# Arduino-RedBoard.net
KiCad netlist of a schematic drawn in Altium Designer
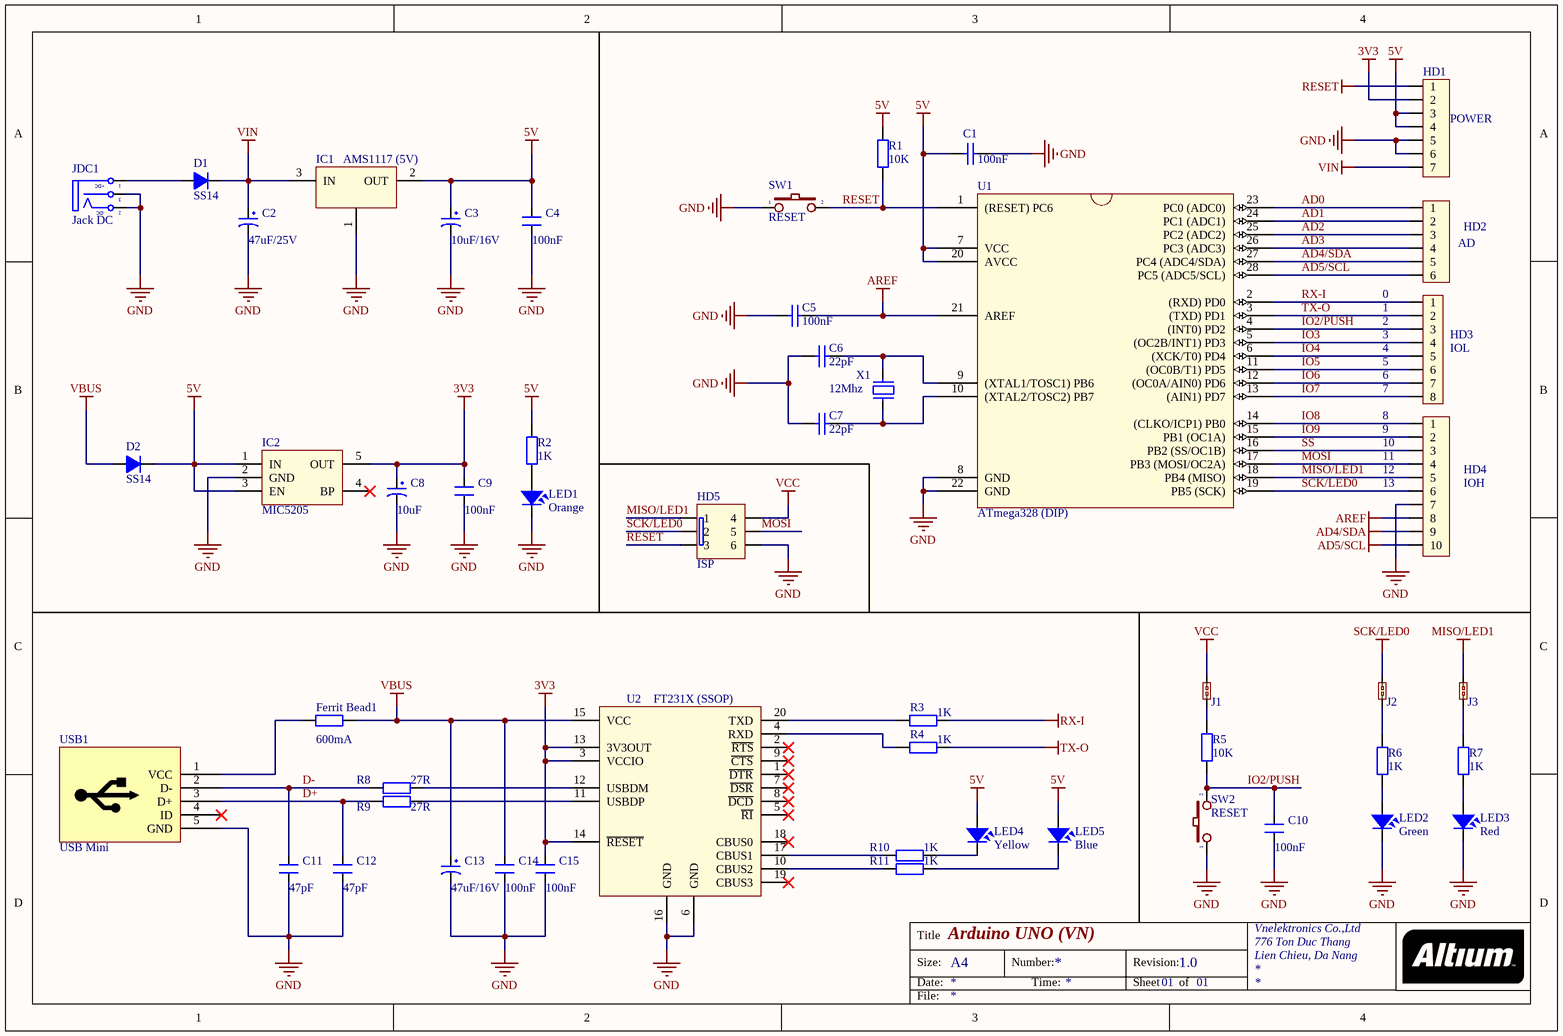
[diagram p0: Arduino-RedBoard.SchDoc]

(export (version "E")
  (design (tool "Eeschema 10.0.6"))
  (components
    (comp (ref "C1")
      (value "100nF")
      (footprint "CAPNTO2.54-3.05x1.78A")
      (description "CAP NPO CAPNTO 1nF 100V 10%")
      (fields (field (name "Comment") "5AK102KABAA"))
      (libsource (lib "lpson") (part "5AK102KABAA"))
    )
    (comp (ref "C2") (value "47uF/25V") (footprint "CP1/2") (libsource (lib "VNELEK") (part "CP1")))
    (comp (ref "C3")
      (value "10uF/16V")
      (footprint "CP1/2")
      (description "Cap P  0,1uF < 22uF , 16 - 50V")
      (libsource (lib "VNELEK") (part "CP1"))
    )
    (comp (ref "C4")
      (value "100nF")
      (footprint "CN2")
      (description "Cap np 104 => 105pF")
      (libsource (lib "VNELEK") (part "CN2"))
    )
    (comp (ref "C5")
      (value "100nF")
      (footprint "CAPNTO2.54-3.05x1.78A")
      (description "CAP NPO CAPNTO 1nF 100V 10%")
      (fields (field (name "Comment") "5AK102KABAA"))
      (libsource (lib "lpson") (part "5AK102KABAA"))
    )
    (comp (ref "C6")
      (value "22pF")
      (footprint "CAPNTO2.54-3.05x1.78A")
      (description "CAP NPO CAPNTO 1nF 100V 10%")
      (fields (field (name "Comment") "5AK102KABAA"))
      (libsource (lib "lpson") (part "5AK102KABAA"))
    )
    (comp (ref "C7")
      (value "22pF")
      (footprint "CAPNTO2.54-3.05x1.78A")
      (description "CAP NPO CAPNTO 1nF 100V 10%")
      (fields (field (name "Comment") "5AK102KABAA"))
      (libsource (lib "lpson") (part "5AK102KABAA"))
    )
    (comp (ref "C8")
      (value "10uF")
      (footprint "CP1/2")
      (description "Cap P  0,1uF < 22uF , 16 - 50V")
      (libsource (lib "VNELEK") (part "CP1"))
    )
    (comp (ref "C9")
      (value "100nF")
      (footprint "CN2")
      (description "Cap np 104 => 105pF")
      (libsource (lib "VNELEK") (part "CN2"))
    )
    (comp (ref "C10")
      (value "100nF")
      (footprint "CN2")
      (description "Cap np 104 => 105pF")
      (libsource (lib "VNELEK") (part "CN2"))
    )
    (comp (ref "C11")
      (value "47pF")
      (footprint "CN2")
      (description "Cap np 104 => 105pF")
      (libsource (lib "VNELEK") (part "CN2"))
    )
    (comp (ref "C12")
      (value "47pF")
      (footprint "CN2")
      (description "Cap np 104 => 105pF")
      (libsource (lib "VNELEK") (part "CN2"))
    )
    (comp (ref "C13") (value "47uF/16V") (footprint "CP1/2") (libsource (lib "VNELEK") (part "CP1")))
    (comp (ref "C14")
      (value "100nF")
      (footprint "CN2")
      (description "Cap np 104 => 105pF")
      (libsource (lib "VNELEK") (part "CN2"))
    )
    (comp (ref "C15")
      (value "100nF")
      (footprint "CN2")
      (description "Cap np 104 => 105pF")
      (libsource (lib "VNELEK") (part "CN2"))
    )
    (comp (ref "D1")
      (value "SS14")
      (footprint "D1A")
      (description "Diode 1A")
      (libsource (lib "VNELEK") (part "D1A"))
    )
    (comp (ref "D2")
      (value "SS14")
      (footprint "D1A")
      (description "Diode 1A")
      (libsource (lib "VNELEK") (part "D1A"))
    )
    (comp (ref "Ferrit Bead1")
      (value "600mA")
      (footprint "AXIAL-0.4")
      (description "Ferrit Bead")
      (libsource (lib "") (part "Res2_2"))
    )
    (comp (ref "HD1") (value "POWER") (description "Header 7") (libsource (lib "Tran Tuan") (part "Hed7")))
    (comp (ref "HD2") (value "AD") (description "Header 6") (libsource (lib "Tran Tuan") (part "Hed6")))
    (comp (ref "HD3")
      (value "IOL")
      (footprint "HED8")
      (description "Hedear 8")
      (fields (field (name "CREAT BY") "VanDungEvn@Gmail.com"))
      (libsource (lib "VNELEK") (part "Hed8"))
    )
    (comp (ref "HD4") (value "IOH") (description "Header 10") (libsource (lib "Tran Tuan") (part "Hed10")))
    (comp (ref "HD5") (value "ISP") (description "Header 3x2") (libsource (lib "Tran Tuan") (part "HED3x2")))
    (comp (ref "IC1")
      (value "AMS1117 (5V)")
      (description "1A LOW DROPOUT VOLTAGE REGULATOR")
      (libsource (lib "Tran Tuan") (part "AMS1117"))
    )
    (comp (ref "IC2")
      (value "MIC5205")
      (description "150mA Low  -  Noise LDO Regulator")
      (libsource (lib "Tran Tuan") (part "MIC5205"))
    )
    (comp (ref "J1") (value "Short Jump") (libsource (lib "Tran Tuan") (part "ShortJump")))
    (comp (ref "J2") (value "Short Jump") (libsource (lib "Tran Tuan") (part "ShortJump")))
    (comp (ref "J3") (value "Short Jump") (libsource (lib "Tran Tuan") (part "ShortJump")))
    (comp (ref "JDC1")
      (value "Jack DC")
      (footprint "DC-IN")
      (description "Jac DC input")
      (libsource (lib "VNELEK") (part "DCIN"))
    )
    (comp (ref "LED1")
      (value "Orange")
      (footprint "LED-3")
      (description "LED Single colour Green and Red")
      (libsource (lib "VNELEK") (part "LED"))
    )
    (comp (ref "LED2")
      (value "Green")
      (footprint "LED-3")
      (description "LED Single colour Green and Red")
      (libsource (lib "VNELEK") (part "LED"))
    )
    (comp (ref "LED3")
      (value "Red")
      (footprint "LED-3")
      (description "LED Single colour Green and Red")
      (libsource (lib "VNELEK") (part "LED"))
    )
    (comp (ref "LED4")
      (value "Yellow")
      (footprint "LED-3")
      (description "LED Single colour Green and Red")
      (libsource (lib "VNELEK") (part "LED"))
    )
    (comp (ref "LED5")
      (value "Blue")
      (footprint "LED-3")
      (description "LED Single colour Green and Red")
      (libsource (lib "VNELEK") (part "LED"))
    )
    (comp (ref "R1")
      (value "10K")
      (footprint "AXIAL-0.4")
      (description "Resistor")
      (fields (field (name "Comment") "Res2") (field (name "PUBLISHER") "Altium Limited"))
      (libsource (lib "Miscellaneous Devices") (part "Res2"))
    )
    (comp (ref "R2")
      (value "1K")
      (footprint "AXIAL-0.4")
      (description "Resistor")
      (fields (field (name "Comment") "Res2") (field (name "PUBLISHER") "Altium Limited"))
      (libsource (lib "Miscellaneous Devices") (part "Res2"))
    )
    (comp (ref "R3")
      (value "1K")
      (footprint "AXIAL-0.4")
      (description "Resistor")
      (fields (field (name "Comment") "Res2") (field (name "PUBLISHER") "Altium Limited"))
      (libsource (lib "") (part "Res2_2"))
    )
    (comp (ref "R4")
      (value "1K")
      (footprint "AXIAL-0.4")
      (description "Resistor")
      (fields (field (name "Comment") "Res2") (field (name "PUBLISHER") "Altium Limited"))
      (libsource (lib "") (part "Res2_2"))
    )
    (comp (ref "R5")
      (value "10K")
      (footprint "AXIAL-0.4")
      (description "Resistor")
      (fields (field (name "Comment") "Res2") (field (name "PUBLISHER") "Altium Limited"))
      (libsource (lib "Miscellaneous Devices") (part "Res2"))
    )
    (comp (ref "R6")
      (value "1K")
      (footprint "AXIAL-0.4")
      (description "Resistor")
      (fields (field (name "Comment") "Res2") (field (name "PUBLISHER") "Altium Limited"))
      (libsource (lib "Miscellaneous Devices") (part "Res2"))
    )
    (comp (ref "R7")
      (value "1K")
      (footprint "AXIAL-0.4")
      (description "Resistor")
      (fields (field (name "Comment") "Res2") (field (name "PUBLISHER") "Altium Limited"))
      (libsource (lib "Miscellaneous Devices") (part "Res2"))
    )
    (comp (ref "R8")
      (value "27R")
      (footprint "AXIAL-0.4")
      (description "Resistor")
      (fields (field (name "Comment") "Res2") (field (name "PUBLISHER") "Altium Limited"))
      (libsource (lib "") (part "Res2_1"))
    )
    (comp (ref "R9")
      (value "27R")
      (footprint "AXIAL-0.4")
      (description "Resistor")
      (fields (field (name "Comment") "Res2") (field (name "PUBLISHER") "Altium Limited"))
      (libsource (lib "") (part "Res2_1"))
    )
    (comp (ref "R10")
      (value "1K")
      (footprint "AXIAL-0.4")
      (description "Resistor")
      (fields (field (name "Comment") "Res2") (field (name "PUBLISHER") "Altium Limited"))
      (libsource (lib "") (part "Res2_1"))
    )
    (comp (ref "R11")
      (value "1K")
      (footprint "AXIAL-0.4")
      (description "Resistor")
      (fields (field (name "Comment") "Res2") (field (name "PUBLISHER") "Altium Limited"))
      (libsource (lib "") (part "Res2_1"))
    )
    (comp (ref "SW1")
      (value "RESET")
      (footprint "SW2")
      (description "Switch button 2 pin")
      (libsource (lib "VNELEK") (part "SW2"))
    )
    (comp (ref "SW2")
      (value "RESET")
      (footprint "SW2")
      (description "Switch button 2 pin")
      (libsource (lib "VNELEK") (part "SW2"))
    )
    (comp (ref "U1")
      (value "ATmega328 (DIP)")
      (description "Atmel 8-bit Microcontroller")
      (libsource (lib "Tran Tuan") (part "ATmega328_1"))
    )
    (comp (ref "U2")
      (value "FT231X (SSOP)")
      (description "FT231Z (SSOP) - USB to UART")
      (libsource (lib "Tran Tuan") (part "FT231X"))
    )
    (comp (ref "USB1") (value "USB Mini") (footprint "USB_B_MINI") (libsource (lib "VNELEK") (part "USB_M")))
    (comp (ref "X1")
      (value "12Mhz")
      (footprint "CRYSTAL")
      (description "Crystal For all Crystal 2pin.")
      (libsource (lib "lpson") (part "XT2"))
    )
  )
  (nets
    (net (code "1") (name "/AD0") (class "Default")
      (node (ref "HD2") (pin "1") (pinfunction "1_1") (pintype "passive"))
      (node (ref "U1") (pin "23") (pinfunction "PC0_(ADC0)_23") (pintype "bidirectional"))
    )
    (net (code "2") (name "/AD1") (class "Default")
      (node (ref "HD2") (pin "2") (pinfunction "2_2") (pintype "passive"))
      (node (ref "U1") (pin "24") (pinfunction "PC1_(ADC1)_24") (pintype "bidirectional"))
    )
    (net (code "3") (name "/AD2") (class "Default")
      (node (ref "HD2") (pin "3") (pinfunction "3_3") (pintype "passive"))
      (node (ref "U1") (pin "25") (pinfunction "PC2_(ADC2)_25") (pintype "bidirectional"))
    )
    (net (code "4") (name "/AD3") (class "Default")
      (node (ref "HD2") (pin "4") (pinfunction "4_4") (pintype "passive"))
      (node (ref "U1") (pin "26") (pinfunction "PC3_(ADC3)_26") (pintype "bidirectional"))
    )
    (net (code "5") (name "/D+") (class "Default")
      (node (ref "C12") (pin "2") (pinfunction "2_2") (pintype "passive"))
      (node (ref "R9") (pin "2") (pinfunction "2_2") (pintype "passive"))
      (node (ref "USB1") (pin "3") (pinfunction "D+_3") (pintype "passive"))
    )
    (net (code "6") (name "/D-") (class "Default")
      (node (ref "C11") (pin "2") (pinfunction "2_2") (pintype "passive"))
      (node (ref "R8") (pin "2") (pinfunction "2_2") (pintype "passive"))
      (node (ref "USB1") (pin "2") (pinfunction "D-_2") (pintype "passive"))
    )
    (net (code "7") (name "/IO2{slash}PUSH") (class "Default")
      (node (ref "C10") (pin "2") (pinfunction "2_2") (pintype "passive"))
      (node (ref "HD3") (pin "3") (pinfunction "3_3") (pintype "passive"))
      (node (ref "R5") (pin "1") (pinfunction "1_1") (pintype "passive"))
      (node (ref "SW2") (pin "2") (pinfunction "2_2") (pintype "passive"))
      (node (ref "U1") (pin "4") (pinfunction "(INT0)_PD2_4") (pintype "bidirectional"))
    )
    (net (code "8") (name "/IO3") (class "Default")
      (node (ref "HD3") (pin "4") (pinfunction "4_4") (pintype "passive"))
      (node (ref "U1") (pin "5") (pinfunction "(OC2B/INT1)_PD3_5") (pintype "bidirectional"))
    )
    (net (code "9") (name "/IO4") (class "Default")
      (node (ref "HD3") (pin "5") (pinfunction "5_5") (pintype "passive"))
      (node (ref "U1") (pin "6") (pinfunction "(XCK/T0)_PD4_6") (pintype "bidirectional"))
    )
    (net (code "10") (name "/IO5") (class "Default")
      (node (ref "HD3") (pin "6") (pinfunction "6_6") (pintype "passive"))
      (node (ref "U1") (pin "11") (pinfunction "(OC0B/T1)_PD5_11") (pintype "bidirectional"))
    )
    (net (code "11") (name "/IO6") (class "Default")
      (node (ref "HD3") (pin "7") (pinfunction "7_7") (pintype "passive"))
      (node (ref "U1") (pin "12") (pinfunction "(OC0A/AIN0)_PD6_12") (pintype "bidirectional"))
    )
    (net (code "12") (name "/IO7") (class "Default")
      (node (ref "HD3") (pin "8") (pinfunction "8_8") (pintype "passive"))
      (node (ref "U1") (pin "13") (pinfunction "(AIN1)_PD7_13") (pintype "bidirectional"))
    )
    (net (code "13") (name "/IO8") (class "Default")
      (node (ref "HD4") (pin "1") (pinfunction "1_1") (pintype "passive"))
      (node (ref "U1") (pin "14") (pinfunction "(CLKO/ICP1)_PB0_14") (pintype "bidirectional"))
    )
    (net (code "14") (name "/IO9") (class "Default")
      (node (ref "HD4") (pin "2") (pinfunction "2_2") (pintype "passive"))
      (node (ref "U1") (pin "15") (pinfunction "PB1_(OC1A)_15") (pintype "bidirectional"))
    )
    (net (code "15") (name "/MOSI") (class "Default")
      (node (ref "HD4") (pin "4") (pinfunction "4_4") (pintype "passive"))
      (node (ref "HD5") (pin "5") (pinfunction "5_5") (pintype "passive"))
      (node (ref "U1") (pin "17") (pinfunction "PB3_(MOSI/OC2A)_17") (pintype "bidirectional"))
    )
    (net (code "16") (name "/SS") (class "Default")
      (node (ref "HD4") (pin "3") (pinfunction "3_3") (pintype "passive"))
      (node (ref "U1") (pin "16") (pinfunction "PB2_(SS/OC1B)_16") (pintype "bidirectional"))
    )
    (net (code "17") (name "3V3") (class "Default")
      (node (ref "C15") (pin "2") (pinfunction "2_2") (pintype "passive"))
      (node (ref "C8") (pin "1") (pinfunction "1_1") (pintype "passive"))
      (node (ref "C9") (pin "2") (pinfunction "2_2") (pintype "passive"))
      (node (ref "HD1") (pin "2") (pinfunction "2_2") (pintype "passive"))
      (node (ref "IC2") (pin "5") (pinfunction "OUT_5") (pintype "passive"))
      (node (ref "U2") (pin "13") (pinfunction "3V3OUT_13") (pintype "passive"))
      (node (ref "U2") (pin "14") (pinfunction "~{RESET}_14") (pintype "passive"))
      (node (ref "U2") (pin "3") (pinfunction "VCCIO_3") (pintype "passive"))
    )
    (net (code "18") (name "5V") (class "Default")
      (node (ref "C1") (pin "2") (pinfunction "2_2") (pintype "passive"))
      (node (ref "C3") (pin "1") (pinfunction "1_1") (pintype "passive"))
      (node (ref "C4") (pin "2") (pinfunction "2_2") (pintype "passive"))
      (node (ref "D2") (pin "2") (pinfunction "K_2") (pintype "passive"))
      (node (ref "HD1") (pin "3") (pinfunction "3_3") (pintype "passive"))
      (node (ref "HD1") (pin "4") (pinfunction "4_4") (pintype "passive"))
      (node (ref "IC1") (pin "2") (pinfunction "OUT_2") (pintype "passive"))
      (node (ref "IC2") (pin "1") (pinfunction "IN_1") (pintype "passive"))
      (node (ref "IC2") (pin "3") (pinfunction "EN_3") (pintype "passive"))
      (node (ref "LED4") (pin "1") (pinfunction "1_1") (pintype "passive"))
      (node (ref "LED5") (pin "1") (pinfunction "1_1") (pintype "passive"))
      (node (ref "R1") (pin "2") (pinfunction "2_2") (pintype "passive"))
      (node (ref "R2") (pin "2") (pinfunction "2_2") (pintype "passive"))
      (node (ref "U1") (pin "20") (pinfunction "AVCC_20") (pintype "passive"))
      (node (ref "U1") (pin "7") (pinfunction "VCC_7") (pintype "passive"))
    )
    (net (code "19") (name "AD4{slash}SDA") (class "Default")
      (node (ref "HD2") (pin "5") (pinfunction "5_5") (pintype "passive"))
      (node (ref "HD4") (pin "9") (pinfunction "9_9") (pintype "passive"))
      (node (ref "U1") (pin "27") (pinfunction "PC4_(ADC4/SDA)_27") (pintype "bidirectional"))
    )
    (net (code "20") (name "AD5{slash}SCL") (class "Default")
      (node (ref "HD2") (pin "6") (pinfunction "6_6") (pintype "passive"))
      (node (ref "HD4") (pin "10") (pinfunction "10_10") (pintype "passive"))
      (node (ref "U1") (pin "28") (pinfunction "PC5_(ADC5/SCL)_28") (pintype "bidirectional"))
    )
    (net (code "21") (name "AREF") (class "Default")
      (node (ref "C5") (pin "2") (pinfunction "2_2") (pintype "passive"))
      (node (ref "HD4") (pin "8") (pinfunction "8_8") (pintype "passive"))
      (node (ref "U1") (pin "21") (pinfunction "AREF_21") (pintype "passive"))
    )
    (net (code "22") (name "GND") (class "Default")
      (node (ref "C1") (pin "1") (pinfunction "1_1") (pintype "passive"))
      (node (ref "C10") (pin "1") (pinfunction "1_1") (pintype "passive"))
      (node (ref "C11") (pin "1") (pinfunction "1_1") (pintype "passive"))
      (node (ref "C12") (pin "1") (pinfunction "1_1") (pintype "passive"))
      (node (ref "C13") (pin "2") (pinfunction "2_2") (pintype "passive"))
      (node (ref "C14") (pin "2") (pinfunction "2_2") (pintype "passive"))
      (node (ref "C15") (pin "1") (pinfunction "1_1") (pintype "passive"))
      (node (ref "C2") (pin "2") (pinfunction "2_2") (pintype "passive"))
      (node (ref "C3") (pin "2") (pinfunction "2_2") (pintype "passive"))
      (node (ref "C4") (pin "1") (pinfunction "1_1") (pintype "passive"))
      (node (ref "C5") (pin "1") (pinfunction "1_1") (pintype "passive"))
      (node (ref "C6") (pin "1") (pinfunction "1_1") (pintype "passive"))
      (node (ref "C7") (pin "1") (pinfunction "1_1") (pintype "passive"))
      (node (ref "C8") (pin "2") (pinfunction "2_2") (pintype "passive"))
      (node (ref "C9") (pin "1") (pinfunction "1_1") (pintype "passive"))
      (node (ref "HD1") (pin "5") (pinfunction "5_5") (pintype "passive"))
      (node (ref "HD1") (pin "6") (pinfunction "6_6") (pintype "passive"))
      (node (ref "HD4") (pin "7") (pinfunction "7_7") (pintype "passive"))
      (node (ref "HD5") (pin "6") (pinfunction "6_6") (pintype "passive"))
      (node (ref "IC1") (pin "1") (pinfunction "GND_1") (pintype "passive"))
      (node (ref "IC2") (pin "2") (pinfunction "GND_2") (pintype "passive"))
      (node (ref "JDC1") (pin "2") (pinfunction "TN_2") (pintype "passive"))
      (node (ref "JDC1") (pin "3") (pinfunction "S_3") (pintype "power_in"))
      (node (ref "LED1") (pin "2") (pinfunction "2_2") (pintype "passive"))
      (node (ref "LED2") (pin "2") (pinfunction "2_2") (pintype "passive"))
      (node (ref "LED3") (pin "2") (pinfunction "2_2") (pintype "passive"))
      (node (ref "SW1") (pin "1") (pinfunction "1_1") (pintype "passive"))
      (node (ref "SW2") (pin "1") (pinfunction "1_1") (pintype "passive"))
      (node (ref "U1") (pin "22") (pinfunction "GND_22") (pintype "passive"))
      (node (ref "U1") (pin "8") (pinfunction "GND_8") (pintype "passive"))
      (node (ref "U2") (pin "16") (pinfunction "GND_16") (pintype "passive"))
      (node (ref "U2") (pin "6") (pinfunction "GND_6") (pintype "passive"))
      (node (ref "USB1") (pin "5") (pinfunction "GND_5") (pintype "passive"))
    )
    (net (code "23") (name "MISO{slash}LED1") (class "Default")
      (node (ref "HD4") (pin "5") (pinfunction "5_5") (pintype "passive"))
      (node (ref "HD5") (pin "1") (pinfunction "1_1") (pintype "passive"))
      (node (ref "J3") (pin "2") (pinfunction "2_2") (pintype "passive"))
      (node (ref "U1") (pin "18") (pinfunction "PB4_(MISO)_18") (pintype "bidirectional"))
    )
    (net (code "24") (name "Net-(D1-A)") (class "Default")
      (node (ref "D1") (pin "1") (pinfunction "A_1") (pintype "passive"))
      (node (ref "JDC1") (pin "1") (pinfunction "T_1") (pintype "passive"))
    )
    (net (code "25") (name "Net-(J1-Pad1)") (class "Default")
      (node (ref "J1") (pin "1") (pinfunction "1_1") (pintype "passive"))
      (node (ref "R5") (pin "2") (pinfunction "2_2") (pintype "passive"))
    )
    (net (code "26") (name "Net-(J2-Pad1)") (class "Default")
      (node (ref "J2") (pin "1") (pinfunction "1_1") (pintype "passive"))
      (node (ref "R6") (pin "2") (pinfunction "2_2") (pintype "passive"))
    )
    (net (code "27") (name "Net-(J3-Pad1)") (class "Default")
      (node (ref "J3") (pin "1") (pinfunction "1_1") (pintype "passive"))
      (node (ref "R7") (pin "2") (pinfunction "2_2") (pintype "passive"))
    )
    (net (code "28") (name "Net-(LED1-Pad1)") (class "Default")
      (node (ref "LED1") (pin "1") (pinfunction "1_1") (pintype "passive"))
      (node (ref "R2") (pin "1") (pinfunction "1_1") (pintype "passive"))
    )
    (net (code "29") (name "Net-(LED2-Pad1)") (class "Default")
      (node (ref "LED2") (pin "1") (pinfunction "1_1") (pintype "passive"))
      (node (ref "R6") (pin "1") (pinfunction "1_1") (pintype "passive"))
    )
    (net (code "30") (name "Net-(LED3-Pad1)") (class "Default")
      (node (ref "LED3") (pin "1") (pinfunction "1_1") (pintype "passive"))
      (node (ref "R7") (pin "1") (pinfunction "1_1") (pintype "passive"))
    )
    (net (code "31") (name "Net-(LED4-Pad2)") (class "Default")
      (node (ref "LED4") (pin "2") (pinfunction "2_2") (pintype "passive"))
      (node (ref "R10") (pin "1") (pinfunction "1_1") (pintype "passive"))
    )
    (net (code "32") (name "Net-(LED5-Pad2)") (class "Default")
      (node (ref "LED5") (pin "2") (pinfunction "2_2") (pintype "passive"))
      (node (ref "R11") (pin "1") (pinfunction "1_1") (pintype "passive"))
    )
    (net (code "33") (name "Net-(U1-(XTAL1{slash}TOSC1)_PB6)") (class "Default")
      (node (ref "C6") (pin "2") (pinfunction "2_2") (pintype "passive"))
      (node (ref "U1") (pin "9") (pinfunction "(XTAL1/TOSC1)_PB6_9") (pintype "passive"))
      (node (ref "X1") (pin "2") (pinfunction "2_2") (pintype "passive"))
    )
    (net (code "34") (name "Net-(U1-(XTAL2{slash}TOSC2)_PB7)") (class "Default")
      (node (ref "C7") (pin "2") (pinfunction "2_2") (pintype "passive"))
      (node (ref "U1") (pin "10") (pinfunction "(XTAL2/TOSC2)_PB7_10") (pintype "passive"))
      (node (ref "X1") (pin "1") (pinfunction "1_1") (pintype "passive"))
    )
    (net (code "35") (name "Net-(U2-CBUS1)") (class "Default")
      (node (ref "R10") (pin "2") (pinfunction "2_2") (pintype "passive"))
      (node (ref "U2") (pin "17") (pinfunction "CBUS1_17") (pintype "passive"))
    )
    (net (code "36") (name "Net-(U2-CBUS2)") (class "Default")
      (node (ref "R11") (pin "2") (pinfunction "2_2") (pintype "passive"))
      (node (ref "U2") (pin "10") (pinfunction "CBUS2_10") (pintype "passive"))
    )
    (net (code "37") (name "Net-(U2-RXD)") (class "Default")
      (node (ref "R4") (pin "1") (pinfunction "1_1") (pintype "passive"))
      (node (ref "U2") (pin "4") (pinfunction "RXD_4") (pintype "passive"))
    )
    (net (code "38") (name "Net-(U2-TXD)") (class "Default")
      (node (ref "R3") (pin "1") (pinfunction "1_1") (pintype "passive"))
      (node (ref "U2") (pin "20") (pinfunction "TXD_20") (pintype "passive"))
    )
    (net (code "39") (name "Net-(U2-USBDM)") (class "Default")
      (node (ref "R8") (pin "1") (pinfunction "1_1") (pintype "passive"))
      (node (ref "U2") (pin "12") (pinfunction "USBDM_12") (pintype "passive"))
    )
    (net (code "40") (name "Net-(U2-USBDP)") (class "Default")
      (node (ref "R9") (pin "1") (pinfunction "1_1") (pintype "passive"))
      (node (ref "U2") (pin "11") (pinfunction "USBDP_11") (pintype "passive"))
    )
    (net (code "41") (name "Net-(USB1-VCC)") (class "Default")
      (node (ref "Ferrit Bead1") (pin "1") (pinfunction "1_1") (pintype "passive"))
      (node (ref "USB1") (pin "1") (pinfunction "VCC_1") (pintype "passive"))
    )
    (net (code "42") (name "RESET") (class "Default")
      (node (ref "HD1") (pin "1") (pinfunction "1_1") (pintype "passive"))
      (node (ref "HD5") (pin "3") (pinfunction "3_3") (pintype "passive"))
      (node (ref "R1") (pin "1") (pinfunction "1_1") (pintype "passive"))
      (node (ref "SW1") (pin "2") (pinfunction "2_2") (pintype "passive"))
      (node (ref "U1") (pin "1") (pinfunction "(RESET)_PC6_1") (pintype "passive"))
    )
    (net (code "43") (name "RX-I") (class "Default")
      (node (ref "HD3") (pin "1") (pinfunction "1_1") (pintype "passive"))
      (node (ref "R3") (pin "2") (pinfunction "2_2") (pintype "passive"))
      (node (ref "U1") (pin "2") (pinfunction "(RXD)_PD0_2") (pintype "bidirectional"))
    )
    (net (code "44") (name "SCK{slash}LED0") (class "Default")
      (node (ref "HD4") (pin "6") (pinfunction "6_6") (pintype "passive"))
      (node (ref "HD5") (pin "2") (pinfunction "2_2") (pintype "passive"))
      (node (ref "J2") (pin "2") (pinfunction "2_2") (pintype "passive"))
      (node (ref "U1") (pin "19") (pinfunction "PB5_(SCK)_19") (pintype "bidirectional"))
    )
    (net (code "45") (name "TX-O") (class "Default")
      (node (ref "HD3") (pin "2") (pinfunction "2_2") (pintype "passive"))
      (node (ref "R4") (pin "2") (pinfunction "2_2") (pintype "passive"))
      (node (ref "U1") (pin "3") (pinfunction "(TXD)_PD1_3") (pintype "bidirectional"))
    )
    (net (code "46") (name "VBUS") (class "Default")
      (node (ref "C13") (pin "1") (pinfunction "1_1") (pintype "passive"))
      (node (ref "C14") (pin "1") (pinfunction "1_1") (pintype "passive"))
      (node (ref "D2") (pin "1") (pinfunction "A_1") (pintype "passive"))
      (node (ref "Ferrit Bead1") (pin "2") (pinfunction "2_2") (pintype "passive"))
      (node (ref "U2") (pin "15") (pinfunction "VCC_15") (pintype "passive"))
    )
    (net (code "47") (name "VCC") (class "Default")
      (node (ref "HD5") (pin "4") (pinfunction "4_4") (pintype "passive"))
      (node (ref "J1") (pin "2") (pinfunction "2_2") (pintype "passive"))
    )
    (net (code "48") (name "VIN") (class "Default")
      (node (ref "C2") (pin "1") (pinfunction "1_1") (pintype "passive"))
      (node (ref "D1") (pin "2") (pinfunction "K_2") (pintype "passive"))
      (node (ref "HD1") (pin "7") (pinfunction "7_7") (pintype "passive"))
      (node (ref "IC1") (pin "3") (pinfunction "IN_3") (pintype "passive"))
    )
    (net (code "49") (name "unconnected-(IC2-BP-Pad4)") (class "Default")
      (node (ref "IC2") (pin "4") (pinfunction "BP_4") (pintype "passive+no_connect"))
    )
    (net (code "50") (name "unconnected-(U2-CBUS0-Pad18)") (class "Default")
      (node (ref "U2") (pin "18") (pinfunction "CBUS0_18") (pintype "passive+no_connect"))
    )
    (net (code "51") (name "unconnected-(U2-CBUS3-Pad19)") (class "Default")
      (node (ref "U2") (pin "19") (pinfunction "CBUS3_19") (pintype "passive+no_connect"))
    )
    (net (code "52") (name "unconnected-(U2-~{CTS}-Pad9)") (class "Default")
      (node (ref "U2") (pin "9") (pinfunction "~{CTS}_9") (pintype "passive+no_connect"))
    )
    (net (code "53") (name "unconnected-(U2-~{DCD}-Pad8)") (class "Default")
      (node (ref "U2") (pin "8") (pinfunction "~{DCD}_8") (pintype "passive+no_connect"))
    )
    (net (code "54") (name "unconnected-(U2-~{DSR}-Pad7)") (class "Default")
      (node (ref "U2") (pin "7") (pinfunction "~{DSR}_7") (pintype "passive+no_connect"))
    )
    (net (code "55") (name "unconnected-(U2-~{DTR}-Pad1)") (class "Default")
      (node (ref "U2") (pin "1") (pinfunction "~{DTR}_1") (pintype "passive+no_connect"))
    )
    (net (code "56") (name "unconnected-(U2-~{RI}-Pad5)") (class "Default")
      (node (ref "U2") (pin "5") (pinfunction "~{RI}_5") (pintype "passive+no_connect"))
    )
    (net (code "57") (name "unconnected-(U2-~{RTS}-Pad2)") (class "Default")
      (node (ref "U2") (pin "2") (pinfunction "~{RTS}_2") (pintype "passive+no_connect"))
    )
    (net (code "58") (name "unconnected-(USB1-ID-Pad4)") (class "Default")
      (node (ref "USB1") (pin "4") (pinfunction "ID_4") (pintype "passive+no_connect"))
    )
  )
)
